# sensor.net
KiCad netlist of a schematic drawn in EAGLE
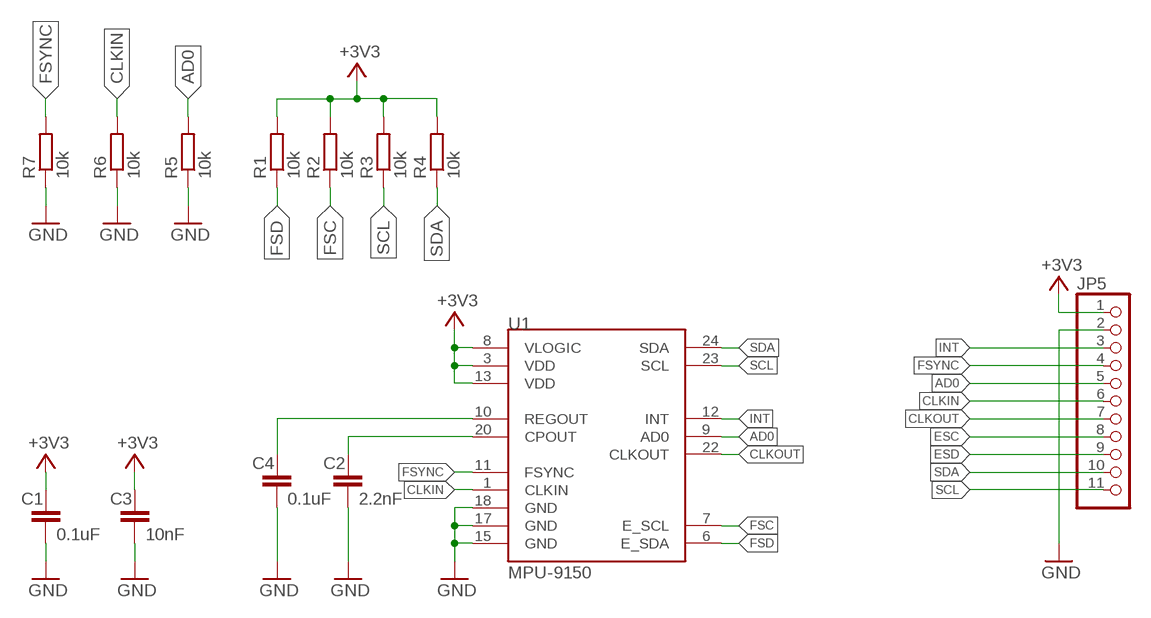
[diagram p0: schematic, sheet 1]

(export (version "E")
  (design (tool "Eeschema 10.0.6"))
  (components
    (comp (ref "C1")
      (value "0.1uF")
      (footprint "eagle-import:C1206K")
      (libsource (lib "eagle-import") (part "C-EUC1206K"))
    )
    (comp (ref "C2")
      (value "2.2nF")
      (footprint "eagle-import:C1206K")
      (libsource (lib "eagle-import") (part "C-EUC1206K"))
    )
    (comp (ref "C3")
      (value "10nF")
      (footprint "eagle-import:C1206K")
      (libsource (lib "eagle-import") (part "C-EUC1206K"))
    )
    (comp (ref "C4")
      (value "0.1uF")
      (footprint "eagle-import:C1206K")
      (libsource (lib "eagle-import") (part "C-EUC1206K"))
    )
    (comp (ref "JP5")
      (value "PINHD-1X11")
      (footprint "eagle-import:1X11")
      (libsource (lib "eagle-import") (part "PINHD-1X11"))
    )
    (comp (ref "R1")
      (value "10k")
      (footprint "eagle-import:R1206")
      (libsource (lib "eagle-import") (part "R-EU_R1206"))
    )
    (comp (ref "R2")
      (value "10k")
      (footprint "eagle-import:R1206")
      (libsource (lib "eagle-import") (part "R-EU_R1206"))
    )
    (comp (ref "R3")
      (value "10k")
      (footprint "eagle-import:R1206")
      (libsource (lib "eagle-import") (part "R-EU_R1206"))
    )
    (comp (ref "R4")
      (value "10k")
      (footprint "eagle-import:R1206")
      (libsource (lib "eagle-import") (part "R-EU_R1206"))
    )
    (comp (ref "R5")
      (value "10k")
      (footprint "eagle-import:R1206")
      (libsource (lib "eagle-import") (part "R-EU_R1206"))
    )
    (comp (ref "R6")
      (value "10k")
      (footprint "eagle-import:R1206")
      (libsource (lib "eagle-import") (part "R-EU_R1206"))
    )
    (comp (ref "R7")
      (value "10k")
      (footprint "eagle-import:R1206")
      (libsource (lib "eagle-import") (part "R-EU_R1206"))
    )
    (comp (ref "U1")
      (value "MPU-9150")
      (footprint "eagle-import:QFN-24-NP")
      (libsource (lib "eagle-import") (part "MPU-9150QFN-24-NP"))
    )
  )
  (nets
    (net (code "1") (name "+3V3") (class "Default")
      (node (ref "C1") (pin "1") (pinfunction "1_1") (pintype "passive"))
      (node (ref "C3") (pin "1") (pinfunction "1_1") (pintype "passive"))
      (node (ref "JP5") (pin "1") (pinfunction "1_1") (pintype "passive"))
      (node (ref "R1") (pin "2") (pinfunction "2_2") (pintype "passive"))
      (node (ref "R2") (pin "2") (pinfunction "2_2") (pintype "passive"))
      (node (ref "R3") (pin "2") (pinfunction "2_2") (pintype "passive"))
      (node (ref "R4") (pin "2") (pinfunction "2_2") (pintype "passive"))
      (node (ref "U1") (pin "13") (pinfunction "VDD_13") (pintype "bidirectional"))
      (node (ref "U1") (pin "3") (pinfunction "VDD_3") (pintype "bidirectional"))
      (node (ref "U1") (pin "8") (pinfunction "VLOGIC_8") (pintype "bidirectional"))
    )
    (net (code "2") (name "AD0") (class "Default")
      (node (ref "JP5") (pin "5") (pinfunction "5_5") (pintype "passive"))
      (node (ref "R5") (pin "2") (pinfunction "2_2") (pintype "passive"))
      (node (ref "U1") (pin "9") (pinfunction "AD0_9") (pintype "bidirectional"))
    )
    (net (code "3") (name "CLKIN") (class "Default")
      (node (ref "JP5") (pin "6") (pinfunction "6_6") (pintype "passive"))
      (node (ref "R6") (pin "2") (pinfunction "2_2") (pintype "passive"))
      (node (ref "U1") (pin "1") (pinfunction "CLKIN_1") (pintype "bidirectional"))
    )
    (net (code "4") (name "CLKOUT") (class "Default")
      (node (ref "JP5") (pin "7") (pinfunction "7_7") (pintype "passive"))
      (node (ref "U1") (pin "22") (pinfunction "CLKOUT_22") (pintype "bidirectional"))
    )
    (net (code "5") (name "ESC") (class "Default")
      (node (ref "JP5") (pin "8") (pinfunction "8_8") (pintype "passive"))
    )
    (net (code "6") (name "ESD") (class "Default")
      (node (ref "JP5") (pin "9") (pinfunction "9_9") (pintype "passive"))
    )
    (net (code "7") (name "FSC") (class "Default")
      (node (ref "R2") (pin "1") (pinfunction "1_1") (pintype "passive"))
      (node (ref "U1") (pin "7") (pinfunction "E_SCL_7") (pintype "bidirectional"))
    )
    (net (code "8") (name "FSD") (class "Default")
      (node (ref "R1") (pin "1") (pinfunction "1_1") (pintype "passive"))
      (node (ref "U1") (pin "6") (pinfunction "E_SDA_6") (pintype "bidirectional"))
    )
    (net (code "9") (name "FSYNC") (class "Default")
      (node (ref "JP5") (pin "4") (pinfunction "4_4") (pintype "passive"))
      (node (ref "R7") (pin "2") (pinfunction "2_2") (pintype "passive"))
      (node (ref "U1") (pin "11") (pinfunction "FSYNC_11") (pintype "bidirectional"))
    )
    (net (code "10") (name "GND") (class "Default")
      (node (ref "C1") (pin "2") (pinfunction "2_2") (pintype "passive"))
      (node (ref "C2") (pin "2") (pinfunction "2_2") (pintype "passive"))
      (node (ref "C3") (pin "2") (pinfunction "2_2") (pintype "passive"))
      (node (ref "C4") (pin "2") (pinfunction "2_2") (pintype "passive"))
      (node (ref "JP5") (pin "2") (pinfunction "2_2") (pintype "passive"))
      (node (ref "R5") (pin "1") (pinfunction "1_1") (pintype "passive"))
      (node (ref "R6") (pin "1") (pinfunction "1_1") (pintype "passive"))
      (node (ref "R7") (pin "1") (pinfunction "1_1") (pintype "passive"))
      (node (ref "U1") (pin "15") (pinfunction "GND_15") (pintype "bidirectional"))
      (node (ref "U1") (pin "17") (pinfunction "GND_17") (pintype "bidirectional"))
      (node (ref "U1") (pin "18") (pinfunction "GND_18") (pintype "bidirectional"))
    )
    (net (code "11") (name "INT") (class "Default")
      (node (ref "JP5") (pin "3") (pinfunction "3_3") (pintype "passive"))
      (node (ref "U1") (pin "12") (pinfunction "INT_12") (pintype "bidirectional"))
    )
    (net (code "12") (name "Net-(U1-CPOUT)") (class "Default")
      (node (ref "C2") (pin "1") (pinfunction "1_1") (pintype "passive"))
      (node (ref "U1") (pin "20") (pinfunction "CPOUT_20") (pintype "bidirectional"))
    )
    (net (code "13") (name "Net-(U1-REGOUT)") (class "Default")
      (node (ref "C4") (pin "1") (pinfunction "1_1") (pintype "passive"))
      (node (ref "U1") (pin "10") (pinfunction "REGOUT_10") (pintype "bidirectional"))
    )
    (net (code "14") (name "SCL") (class "Default")
      (node (ref "JP5") (pin "11") (pinfunction "11_11") (pintype "passive"))
      (node (ref "R3") (pin "1") (pinfunction "1_1") (pintype "passive"))
      (node (ref "U1") (pin "23") (pinfunction "SCL_23") (pintype "bidirectional"))
    )
    (net (code "15") (name "SDA") (class "Default")
      (node (ref "JP5") (pin "10") (pinfunction "10_10") (pintype "passive"))
      (node (ref "R4") (pin "1") (pinfunction "1_1") (pintype "passive"))
      (node (ref "U1") (pin "24") (pinfunction "SDA_24") (pintype "bidirectional"))
    )
  )
)
